# PDOC.net
KiCad netlist of a schematic drawn in Altium Designer
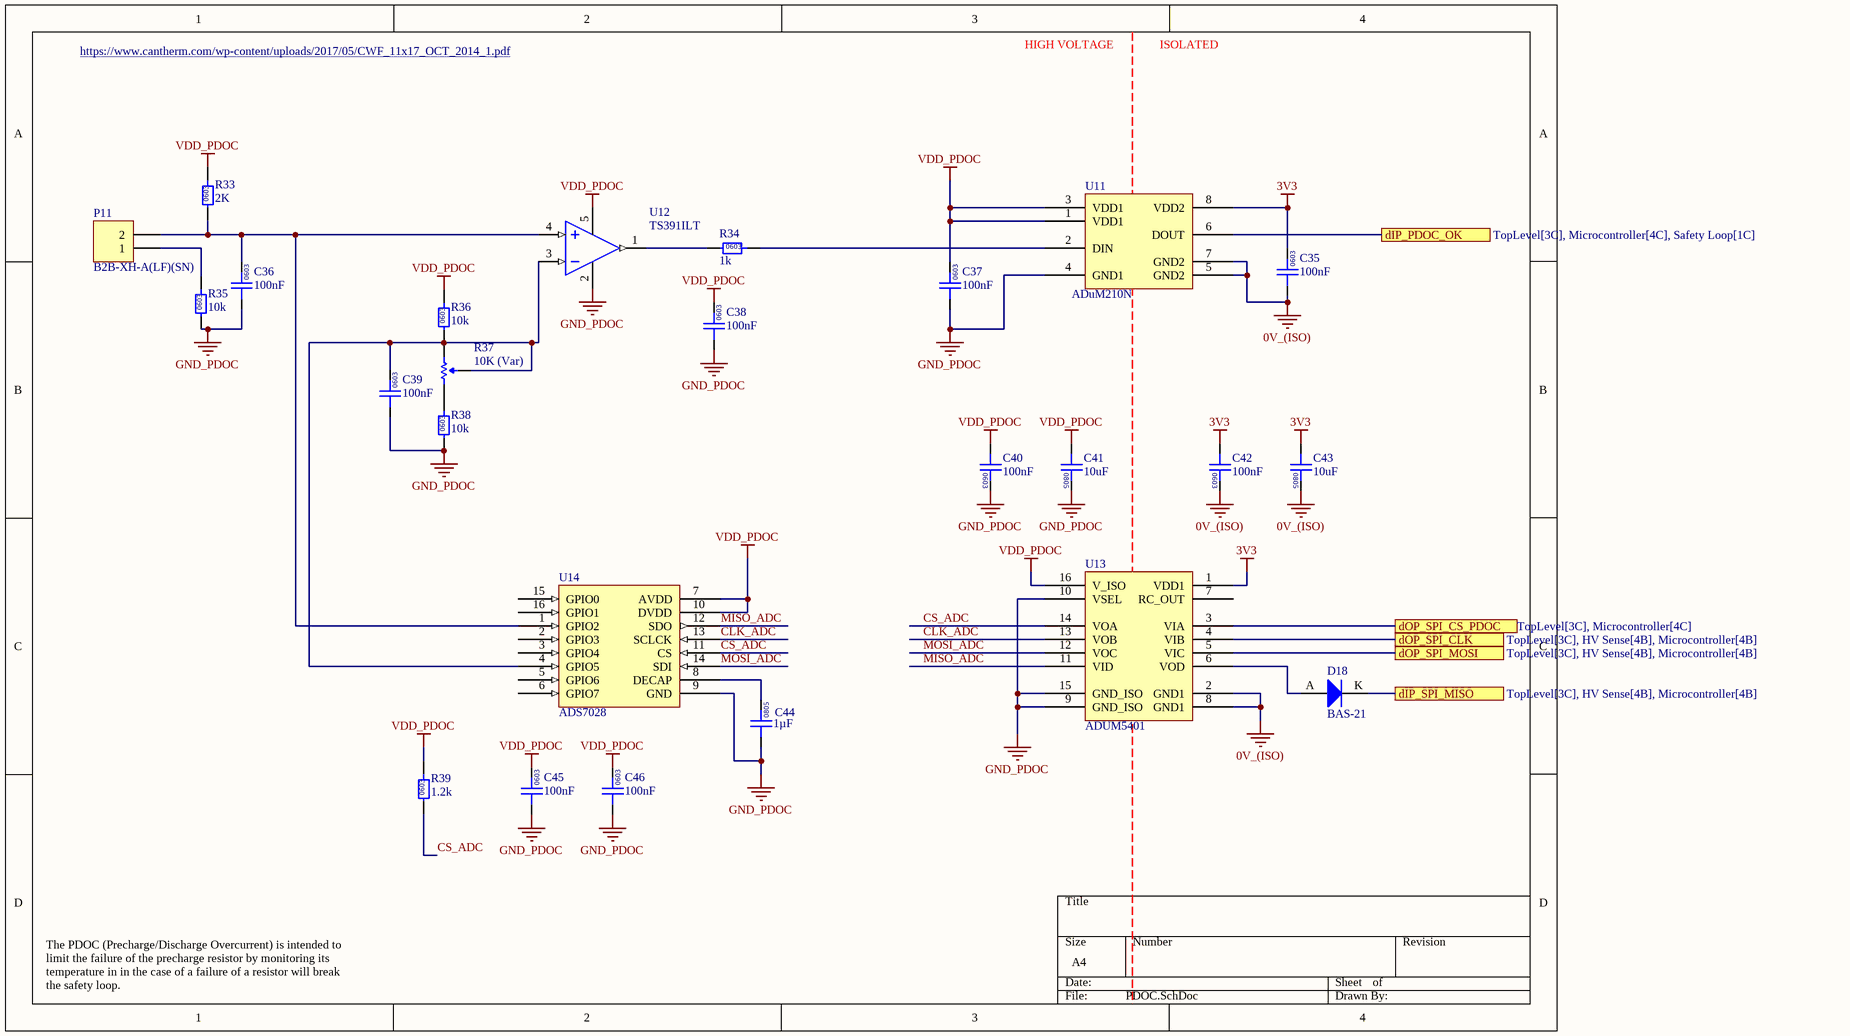
[diagram p0: PDOC.SchDoc]

(export (version "E")
  (design (tool "Eeschema 10.0.6"))
  (components
    (comp (ref "C35")
      (value "100nF")
      (footprint "0603")
      (fields
        (field (name "PART NUMBER") "GCM188L81H104KA57D")
        (field (name "MANUFACTURER") "muRata")
        (field (name "TOLERANCE") "±10%")
      )
      (libsource (lib "ts_standard_library") (part "Capacitor 0603"))
    )
    (comp (ref "C36")
      (value "100nF")
      (footprint "0603")
      (fields
        (field (name "PART NUMBER") "GCM188L81H104KA57D")
        (field (name "MANUFACTURER") "muRata")
        (field (name "TOLERANCE") "±10%")
      )
      (libsource (lib "ts_standard_library") (part "Capacitor 0603"))
    )
    (comp (ref "C37")
      (value "100nF")
      (footprint "0603")
      (fields
        (field (name "PART NUMBER") "GCM188L81H104KA57D")
        (field (name "MANUFACTURER") "muRata")
        (field (name "TOLERANCE") "±10%")
      )
      (libsource (lib "ts_standard_library") (part "Capacitor 0603"))
    )
    (comp (ref "C38")
      (value "100nF")
      (footprint "0603")
      (fields
        (field (name "PART NUMBER") "GCM188L81H104KA57D")
        (field (name "MANUFACTURER") "muRata")
        (field (name "TOLERANCE") "±10%")
      )
      (libsource (lib "ts_standard_library") (part "Capacitor 0603"))
    )
    (comp (ref "C39")
      (value "100nF")
      (footprint "0603")
      (fields
        (field (name "PART NUMBER") "GCM188L81H104KA57D")
        (field (name "MANUFACTURER") "muRata")
        (field (name "TOLERANCE") "±10%")
      )
      (libsource (lib "ts_standard_library") (part "Capacitor 0603"))
    )
    (comp (ref "C40")
      (value "100nF")
      (footprint "0603")
      (fields
        (field (name "PART NUMBER") "GCM188L81H104KA57D")
        (field (name "MANUFACTURER") "muRata")
        (field (name "TOLERANCE") "±10%")
      )
      (libsource (lib "ts_standard_library") (part "Capacitor 0603"))
    )
    (comp (ref "C41")
      (value "10uF")
      (footprint "0805")
      (fields
        (field (name "PART NUMBER") "GRM21BR6YA106KE43L")
        (field (name "MANUFACTURER") "muRata")
        (field (name "TOLERANCE") "10%")
      )
      (libsource (lib "ts_standard_library") (part "Capacitor 0805"))
    )
    (comp (ref "C42")
      (value "100nF")
      (footprint "0603")
      (fields
        (field (name "PART NUMBER") "GCM188L81H104KA57D")
        (field (name "MANUFACTURER") "muRata")
        (field (name "TOLERANCE") "±10%")
      )
      (libsource (lib "ts_standard_library") (part "Capacitor 0603"))
    )
    (comp (ref "C43")
      (value "10uF")
      (footprint "0805")
      (fields
        (field (name "PART NUMBER") "GRM21BR6YA106KE43L")
        (field (name "MANUFACTURER") "muRata")
        (field (name "TOLERANCE") "10%")
      )
      (libsource (lib "ts_standard_library") (part "Capacitor 0805"))
    )
    (comp (ref "C44")
      (value "1µF")
      (footprint "0805")
      (fields
        (field (name "PART NUMBER") "GCM21BR71H105KA03L")
        (field (name "MANUFACTURER") "muRata")
        (field (name "TOLERANCE") "±10%")
      )
      (libsource (lib "ts_standard_library") (part "Capacitor 0805"))
    )
    (comp (ref "C45")
      (value "100nF")
      (footprint "0603")
      (fields
        (field (name "PART NUMBER") "GCM188L81H104KA57D")
        (field (name "MANUFACTURER") "muRata")
        (field (name "TOLERANCE") "±10%")
      )
      (libsource (lib "ts_standard_library") (part "Capacitor 0603"))
    )
    (comp (ref "C46")
      (value "100nF")
      (footprint "0603")
      (fields
        (field (name "PART NUMBER") "GCM188L81H104KA57D")
        (field (name "MANUFACTURER") "muRata")
        (field (name "TOLERANCE") "±10%")
      )
      (libsource (lib "ts_standard_library") (part "Capacitor 0603"))
    )
    (comp (ref "D18")
      (value "BAS-21")
      (footprint "NEXPERIA_SOT23")
      (fields (field (name "MANUFACTURER") "Nexperia USA Inc."))
      (libsource (lib "ts_standard_library") (part "Diode"))
    )
    (comp (ref "P11")
      (value "B2B-XH-A(LF)(SN)")
      (footprint "XH 2 PIN VERT")
      (fields (field (name "DIGIKEY PART NUMBER") "455-2247-ND") (field (name "CONTACT") "Tin"))
      (libsource (lib "ts_standard_connectors") (part "Header 1x2"))
    )
    (comp (ref "R33")
      (value "2K")
      (footprint "0603")
      (fields
        (field (name "PART NUMBER") "RC0603FR-072KL")
        (field (name "MANUFACTURER") "YAGEO")
        (field (name "TOLERANCE") "0.01")
      )
      (libsource (lib "ts_standard_library") (part "Resistor 0603"))
    )
    (comp (ref "R34")
      (value "1k")
      (footprint "0603")
      (fields
        (field (name "PART NUMBER") "RC0603FR-071KL")
        (field (name "MANUFACTURER") "YAGEO")
        (field (name "TOLERANCE") "0.01")
      )
      (libsource (lib "ts_standard_library") (part "Resistor 0603"))
    )
    (comp (ref "R35")
      (value "10k")
      (footprint "0603")
      (fields
        (field (name "PART NUMBER") "RC0603FR-0710KL")
        (field (name "MANUFACTURER") "YAGEO")
        (field (name "TOLERANCE") "0.01")
      )
      (libsource (lib "ts_standard_library") (part "Resistor 0603"))
    )
    (comp (ref "R36")
      (value "10k")
      (footprint "0603")
      (fields
        (field (name "PART NUMBER") "RC0603FR-0710KL")
        (field (name "MANUFACTURER") "YAGEO")
        (field (name "TOLERANCE") "0.01")
      )
      (libsource (lib "ts_standard_library") (part "Resistor 0603"))
    )
    (comp (ref "R37")
      (value "10K (Var)")
      (footprint "B 3296")
      (fields
        (field (name "PART NUMBER") "3296W-1-103LF")
        (field (name "MANUFACTURER") "Bournes Inc")
        (field (name "TOLERANCE") "0.1")
      )
      (libsource (lib "ts_standard_library") (part "Resistor (Potentiometer)"))
    )
    (comp (ref "R38")
      (value "10k")
      (footprint "0603")
      (fields
        (field (name "PART NUMBER") "RC0603FR-0710KL")
        (field (name "MANUFACTURER") "YAGEO")
        (field (name "TOLERANCE") "0.01")
      )
      (libsource (lib "ts_standard_library") (part "Resistor 0603"))
    )
    (comp (ref "R39")
      (value "1.2k")
      (footprint "0603")
      (fields
        (field (name "PART NUMBER") "RC0603JR-071K2L")
        (field (name "MANUFACTURER") "YAGEO")
        (field (name "TOLERANCE") "0.01")
      )
      (libsource (lib "ts_standard_library") (part "Resistor 0603"))
    )
    (comp (ref "U11")
      (value "ADuM210N")
      (footprint "SOIC-8W")
      (description "DIGITAL ISOLATOR, SINGLE CHANNEL")
      (libsource (lib "Team Swinburne") (part "ADuM210N"))
    )
    (comp (ref "U12")
      (value "TS391ILT")
      (footprint "ON SOT-23-5")
      (description "IC COMP LO PWR SGL V SOT 23-5L")
      (libsource (lib "Team Swinburne") (part "TS391ILT"))
    )
    (comp (ref "U13")
      (value "ADUM5401")
      (footprint "AD 16-SOIC")
      (description "Quad Channel 2.5kV Digital Isolator with isoPower")
      (fields (field (name "MANUFACTURER") "Analogue Devices"))
      (libsource (lib "ts_standard_library") (part "ADUM5401"))
    )
    (comp (ref "U14")
      (value "ADS7028")
      (footprint "WFQN-16")
      (description "IC ADC 12BIT SAR 16WQFN")
      (fields (field (name "PART NUMBER") "ADS7028IRTER") (field (name "MANUFACTURER") "Texas Instruments"))
      (libsource (lib "ts_standard_library") (part "ADS7028IRTER"))
    )
  )
  (nets
    (net (code "1") (name "/CLK_ADC") (class "Default")
      (node (ref "U13") (pin "13") (pinfunction "VOB_13") (pintype "passive"))
      (node (ref "U14") (pin "13") (pinfunction "SCLCK_13") (pintype "input"))
    )
    (net (code "2") (name "/CS_ADC") (class "Default")
      (node (ref "R39") (pin "1") (pinfunction "1_1") (pintype "passive"))
      (node (ref "U13") (pin "14") (pinfunction "VOA_14") (pintype "passive"))
      (node (ref "U14") (pin "11") (pinfunction "CS_11") (pintype "input"))
    )
    (net (code "3") (name "/MISO_ADC") (class "Default")
      (node (ref "U13") (pin "11") (pinfunction "VID_11") (pintype "passive"))
      (node (ref "U14") (pin "12") (pinfunction "SDO_12") (pintype "output"))
    )
    (net (code "4") (name "/MOSI_ADC") (class "Default")
      (node (ref "U13") (pin "12") (pinfunction "VOC_12") (pintype "passive"))
      (node (ref "U14") (pin "14") (pinfunction "SDI_14") (pintype "input"))
    )
    (net (code "5") (name "/dIP_PDOC_OK") (class "Default")
      (node (ref "U11") (pin "6") (pinfunction "DOUT_6") (pintype "passive"))
    )
    (net (code "6") (name "/dIP_SPI_MISO") (class "Default")
      (node (ref "D18") (pin "K") (pinfunction "K_K") (pintype "passive"))
    )
    (net (code "7") (name "/dOP_SPI_CLK") (class "Default")
      (node (ref "U13") (pin "4") (pinfunction "VIB_4") (pintype "passive"))
    )
    (net (code "8") (name "/dOP_SPI_CS_PDOC") (class "Default")
      (node (ref "U13") (pin "3") (pinfunction "VIA_3") (pintype "passive"))
    )
    (net (code "9") (name "/dOP_SPI_MOSI") (class "Default")
      (node (ref "U13") (pin "5") (pinfunction "VIC_5") (pintype "passive"))
    )
    (net (code "10") (name "0V_(ISO)") (class "Default")
      (node (ref "C35") (pin "1") (pinfunction "1_1") (pintype "passive"))
      (node (ref "C42") (pin "2") (pinfunction "2_2") (pintype "passive"))
      (node (ref "C43") (pin "2") (pinfunction "2_2") (pintype "passive"))
      (node (ref "U11") (pin "5") (pinfunction "GND2_5") (pintype "passive"))
      (node (ref "U11") (pin "7") (pinfunction "GND2_7") (pintype "passive"))
      (node (ref "U13") (pin "2") (pinfunction "GND1_2") (pintype "passive"))
      (node (ref "U13") (pin "8") (pinfunction "GND1_8") (pintype "passive"))
    )
    (net (code "11") (name "3V3") (class "Default")
      (node (ref "C35") (pin "2") (pinfunction "2_2") (pintype "passive"))
      (node (ref "C42") (pin "1") (pinfunction "1_1") (pintype "passive"))
      (node (ref "C43") (pin "1") (pinfunction "1_1") (pintype "passive"))
      (node (ref "U11") (pin "8") (pinfunction "VDD2_8") (pintype "passive"))
      (node (ref "U13") (pin "1") (pinfunction "VDD1_1") (pintype "passive"))
    )
    (net (code "12") (name "GND_PDOC") (class "Default")
      (node (ref "C36") (pin "1") (pinfunction "1_1") (pintype "passive"))
      (node (ref "C37") (pin "1") (pinfunction "1_1") (pintype "passive"))
      (node (ref "C38") (pin "1") (pinfunction "1_1") (pintype "passive"))
      (node (ref "C39") (pin "1") (pinfunction "1_1") (pintype "passive"))
      (node (ref "C40") (pin "2") (pinfunction "2_2") (pintype "passive"))
      (node (ref "C41") (pin "2") (pinfunction "2_2") (pintype "passive"))
      (node (ref "C44") (pin "1") (pinfunction "1_1") (pintype "passive"))
      (node (ref "C45") (pin "1") (pinfunction "1_1") (pintype "passive"))
      (node (ref "C46") (pin "1") (pinfunction "1_1") (pintype "passive"))
      (node (ref "R35") (pin "1") (pinfunction "1_1") (pintype "passive"))
      (node (ref "R38") (pin "1") (pinfunction "1_1") (pintype "passive"))
      (node (ref "U11") (pin "4") (pinfunction "GND1_4") (pintype "passive"))
      (node (ref "U12") (pin "2") (pinfunction "VCC-_2") (pintype "power_in"))
      (node (ref "U13") (pin "10") (pinfunction "VSEL_10") (pintype "passive"))
      (node (ref "U13") (pin "15") (pinfunction "GND_ISO_15") (pintype "passive"))
      (node (ref "U13") (pin "9") (pinfunction "GND_ISO_9") (pintype "passive"))
      (node (ref "U14") (pin "9") (pinfunction "GND_9") (pintype "power_in"))
    )
    (net (code "13") (name "Net-(P11-Pad1)") (class "Default")
      (node (ref "P11") (pin "1") (pinfunction "1_1") (pintype "passive"))
      (node (ref "R35") (pin "2") (pinfunction "2_2") (pintype "passive"))
    )
    (net (code "14") (name "Net-(R37-CCW)") (class "Default")
      (node (ref "C39") (pin "2") (pinfunction "2_2") (pintype "passive"))
      (node (ref "R36") (pin "1") (pinfunction "1_1") (pintype "passive"))
      (node (ref "R37") (pin "1") (pinfunction "CCW_1") (pintype "passive"))
      (node (ref "R37") (pin "2") (pinfunction "Wiper_2") (pintype "passive"))
      (node (ref "U12") (pin "3") (pinfunction "IN-_3") (pintype "input"))
      (node (ref "U14") (pin "4") (pinfunction "GPIO5_4") (pintype "input"))
    )
    (net (code "15") (name "Net-(R37-CW)") (class "Default")
      (node (ref "R37") (pin "3") (pinfunction "CW_3") (pintype "passive"))
      (node (ref "R38") (pin "2") (pinfunction "2_2") (pintype "passive"))
    )
    (net (code "16") (name "Net-(U11-DIN)") (class "Default")
      (node (ref "R34") (pin "2") (pinfunction "2_2") (pintype "passive"))
      (node (ref "U11") (pin "2") (pinfunction "DIN_2") (pintype "passive"))
    )
    (net (code "17") (name "Net-(U12-IIN+)") (class "Default")
      (node (ref "C36") (pin "2") (pinfunction "2_2") (pintype "passive"))
      (node (ref "P11") (pin "2") (pinfunction "2_2") (pintype "passive"))
      (node (ref "R33") (pin "1") (pinfunction "1_1") (pintype "passive"))
      (node (ref "U12") (pin "4") (pinfunction "IIN+_4") (pintype "input"))
      (node (ref "U14") (pin "1") (pinfunction "GPIO2_1") (pintype "input"))
    )
    (net (code "18") (name "Net-(U12-OUT)") (class "Default")
      (node (ref "R34") (pin "1") (pinfunction "1_1") (pintype "passive"))
      (node (ref "U12") (pin "1") (pinfunction "OUT_1") (pintype "output"))
    )
    (net (code "19") (name "Net-(U13-VOD)") (class "Default")
      (node (ref "D18") (pin "A") (pinfunction "A_A") (pintype "passive"))
      (node (ref "U13") (pin "6") (pinfunction "VOD_6") (pintype "passive"))
    )
    (net (code "20") (name "Net-(U14-DECAP)") (class "Default")
      (node (ref "C44") (pin "2") (pinfunction "2_2") (pintype "passive"))
      (node (ref "U14") (pin "8") (pinfunction "DECAP_8") (pintype "power_in"))
    )
    (net (code "21") (name "VDD_PDOC") (class "Default")
      (node (ref "C37") (pin "2") (pinfunction "2_2") (pintype "passive"))
      (node (ref "C38") (pin "2") (pinfunction "2_2") (pintype "passive"))
      (node (ref "C40") (pin "1") (pinfunction "1_1") (pintype "passive"))
      (node (ref "C41") (pin "1") (pinfunction "1_1") (pintype "passive"))
      (node (ref "C45") (pin "2") (pinfunction "2_2") (pintype "passive"))
      (node (ref "C46") (pin "2") (pinfunction "2_2") (pintype "passive"))
      (node (ref "R33") (pin "2") (pinfunction "2_2") (pintype "passive"))
      (node (ref "R36") (pin "2") (pinfunction "2_2") (pintype "passive"))
      (node (ref "R39") (pin "2") (pinfunction "2_2") (pintype "passive"))
      (node (ref "U11") (pin "1") (pinfunction "VDD1_1") (pintype "passive"))
      (node (ref "U11") (pin "3") (pinfunction "VDD1_3") (pintype "passive"))
      (node (ref "U12") (pin "5") (pinfunction "VCC+_5") (pintype "power_in"))
      (node (ref "U13") (pin "16") (pinfunction "V_ISO_16") (pintype "passive"))
      (node (ref "U14") (pin "10") (pinfunction "DVDD_10") (pintype "power_in"))
      (node (ref "U14") (pin "7") (pinfunction "AVDD_7") (pintype "power_in"))
    )
    (net (code "22") (name "unconnected-(U13-RC_OUT-Pad7)") (class "Default")
      (node (ref "U13") (pin "7") (pinfunction "RC_OUT_7") (pintype "passive"))
    )
    (net (code "23") (name "unconnected-(U14-GPIO0-Pad15)") (class "Default")
      (node (ref "U14") (pin "15") (pinfunction "GPIO0_15") (pintype "input"))
    )
    (net (code "24") (name "unconnected-(U14-GPIO1-Pad16)") (class "Default")
      (node (ref "U14") (pin "16") (pinfunction "GPIO1_16") (pintype "input"))
    )
    (net (code "25") (name "unconnected-(U14-GPIO3-Pad2)") (class "Default")
      (node (ref "U14") (pin "2") (pinfunction "GPIO3_2") (pintype "input"))
    )
    (net (code "26") (name "unconnected-(U14-GPIO4-Pad3)") (class "Default")
      (node (ref "U14") (pin "3") (pinfunction "GPIO4_3") (pintype "input"))
    )
    (net (code "27") (name "unconnected-(U14-GPIO6-Pad5)") (class "Default")
      (node (ref "U14") (pin "5") (pinfunction "GPIO6_5") (pintype "input"))
    )
    (net (code "28") (name "unconnected-(U14-GPIO7-Pad6)") (class "Default")
      (node (ref "U14") (pin "6") (pinfunction "GPIO7_6") (pintype "input"))
    )
  )
)
